# Hatch2021Trophy0805_2.net
KiCad netlist of a schematic drawn in EAGLE
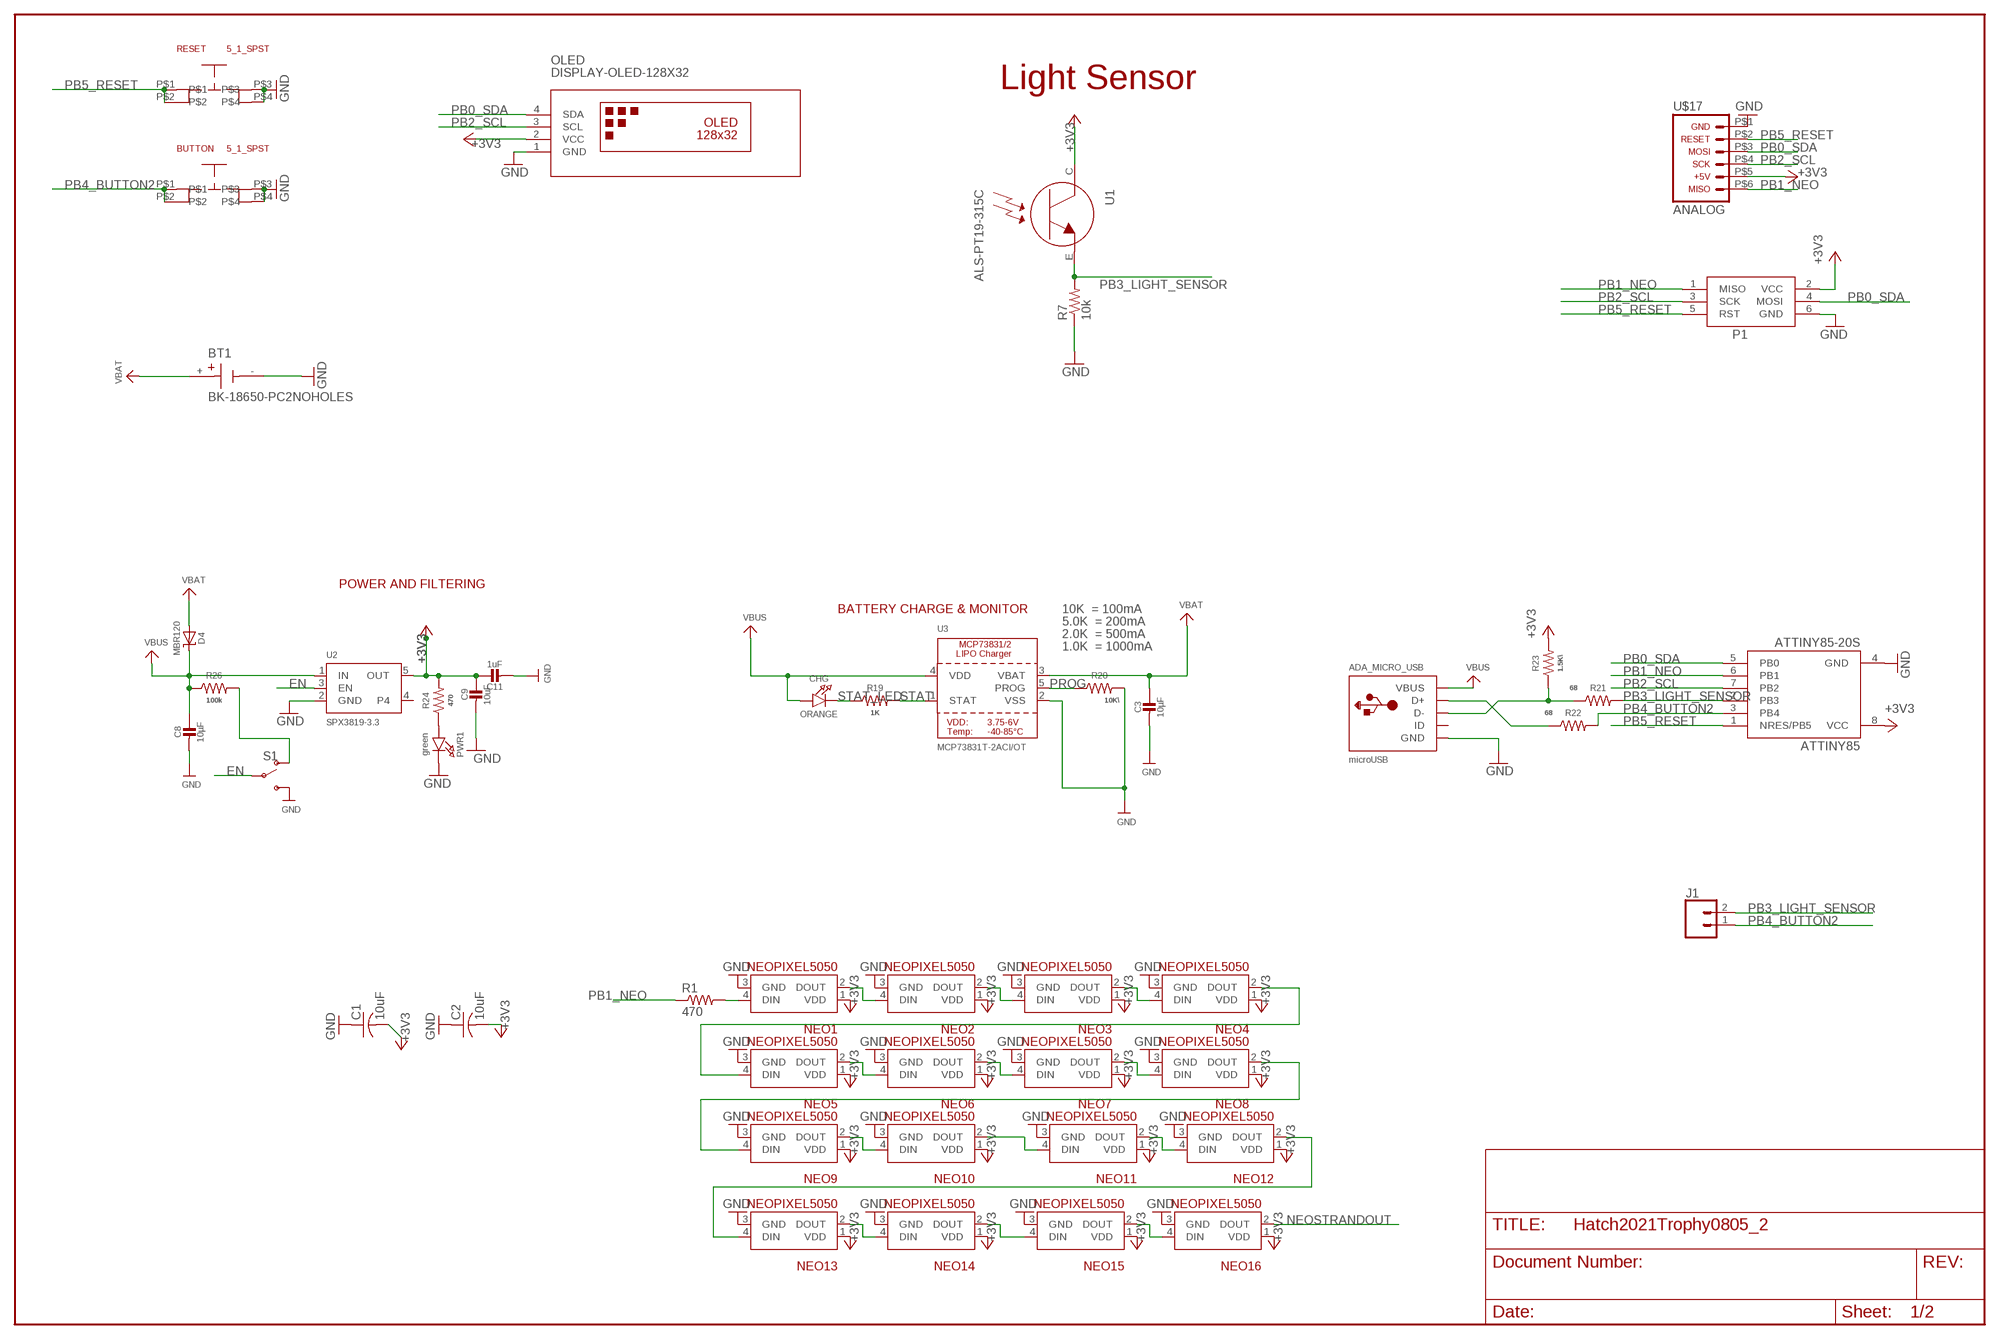
[diagram p0: schematic, sheet 1]

(export (version "E")
  (design (tool "Eeschema 10.0.6"))
  (components
    (comp (ref "ADA_MICRO_USB")
      (value "microUSB")
      (footprint "eagle-import:4UCONN_20329_V2")
      (libsource (lib "eagle-import") (part "USB_MICRO_20329_V2"))
    )
    (comp (ref "ATTINY85")
      (value "ATTINY85-20S")
      (footprint "eagle-import:SOIC8_EIAJ_208MIL")
      (libsource (lib "eagle-import") (part "ATTINY85S-20"))
    )
    (comp (ref "BT1")
      (value "BK-18650-PC2NOHOLES")
      (footprint "eagle-import:BAT_BK-18650-PC2_NOHOLES")
      (libsource (lib "eagle-import") (part "BK-18650-PC2NOHOLES"))
    )
    (comp (ref "BUTTON")
      (value "5_1_SPST")
      (footprint "eagle-import:5_1_SPST")
      (libsource (lib "eagle-import") (part "5_1_SPST"))
    )
    (comp (ref "C1")
      (value "10uF")
      (footprint "eagle-import:C0805")
      (libsource (lib "eagle-import") (part "C-USC0805"))
    )
    (comp (ref "C2")
      (value "10uF")
      (footprint "eagle-import:C0805")
      (libsource (lib "eagle-import") (part "C-USC0805"))
    )
    (comp (ref "C3")
      (value "10µF")
      (footprint "eagle-import:0805-NO@1")
      (libsource (lib "eagle-import") (part "CAP_CERAMIC0805-NOOUTLINE"))
    )
    (comp (ref "C8")
      (value "10µF")
      (footprint "eagle-import:0805-NO@1")
      (libsource (lib "eagle-import") (part "CAP_CERAMIC0805-NOOUTLINE"))
    )
    (comp (ref "C9")
      (value "10uF")
      (footprint "eagle-import:0805-NO@1")
      (libsource (lib "eagle-import") (part "CAP_CERAMIC0805-NOOUTLINE"))
    )
    (comp (ref "C11")
      (value "1uF")
      (footprint "eagle-import:0805-NO@1")
      (libsource (lib "eagle-import") (part "CAP_CERAMIC0805-NOOUTLINE"))
    )
    (comp (ref "CHG")
      (value "ORANGE")
      (footprint "eagle-import:CHIPLED_0805_NOOUTLINE")
      (libsource (lib "eagle-import") (part "LED0805_NOOUTLINE"))
    )
    (comp (ref "D4")
      (value "MBR120")
      (footprint "eagle-import:SOD-123")
      (libsource (lib "eagle-import") (part "DIODE-SCHOTTKYSOD-123"))
    )
    (comp (ref "J1")
      (value "CONN_02")
      (footprint "eagle-import:1X02")
      (libsource (lib "eagle-import") (part "CONN_02"))
    )
    (comp (ref "NEO1")
      (value "NEOPIXEL5050")
      (footprint "eagle-import:NEOPIXEL5050")
      (libsource (lib "eagle-import") (part "NEOPIXEL5050"))
    )
    (comp (ref "NEO2")
      (value "NEOPIXEL5050")
      (footprint "eagle-import:NEOPIXEL5050")
      (libsource (lib "eagle-import") (part "NEOPIXEL5050"))
    )
    (comp (ref "NEO3")
      (value "NEOPIXEL5050")
      (footprint "eagle-import:NEOPIXEL5050")
      (libsource (lib "eagle-import") (part "NEOPIXEL5050"))
    )
    (comp (ref "NEO4")
      (value "NEOPIXEL5050")
      (footprint "eagle-import:NEOPIXEL5050")
      (libsource (lib "eagle-import") (part "NEOPIXEL5050"))
    )
    (comp (ref "NEO5")
      (value "NEOPIXEL5050")
      (footprint "eagle-import:NEOPIXEL5050")
      (libsource (lib "eagle-import") (part "NEOPIXEL5050"))
    )
    (comp (ref "NEO6")
      (value "NEOPIXEL5050")
      (footprint "eagle-import:NEOPIXEL5050")
      (libsource (lib "eagle-import") (part "NEOPIXEL5050"))
    )
    (comp (ref "NEO7")
      (value "NEOPIXEL5050")
      (footprint "eagle-import:NEOPIXEL5050")
      (libsource (lib "eagle-import") (part "NEOPIXEL5050"))
    )
    (comp (ref "NEO8")
      (value "NEOPIXEL5050")
      (footprint "eagle-import:NEOPIXEL5050")
      (libsource (lib "eagle-import") (part "NEOPIXEL5050"))
    )
    (comp (ref "NEO9")
      (value "NEOPIXEL5050")
      (footprint "eagle-import:NEOPIXEL5050")
      (libsource (lib "eagle-import") (part "NEOPIXEL5050"))
    )
    (comp (ref "NEO10")
      (value "NEOPIXEL5050")
      (footprint "eagle-import:NEOPIXEL5050")
      (libsource (lib "eagle-import") (part "NEOPIXEL5050"))
    )
    (comp (ref "NEO11")
      (value "NEOPIXEL5050")
      (footprint "eagle-import:NEOPIXEL5050")
      (libsource (lib "eagle-import") (part "NEOPIXEL5050"))
    )
    (comp (ref "NEO12")
      (value "NEOPIXEL5050")
      (footprint "eagle-import:NEOPIXEL5050")
      (libsource (lib "eagle-import") (part "NEOPIXEL5050"))
    )
    (comp (ref "NEO13")
      (value "NEOPIXEL5050")
      (footprint "eagle-import:NEOPIXEL5050")
      (libsource (lib "eagle-import") (part "NEOPIXEL5050"))
    )
    (comp (ref "NEO14")
      (value "NEOPIXEL5050")
      (footprint "eagle-import:NEOPIXEL5050")
      (libsource (lib "eagle-import") (part "NEOPIXEL5050"))
    )
    (comp (ref "NEO15")
      (value "NEOPIXEL5050")
      (footprint "eagle-import:NEOPIXEL5050")
      (libsource (lib "eagle-import") (part "NEOPIXEL5050"))
    )
    (comp (ref "NEO16")
      (value "NEOPIXEL5050")
      (footprint "eagle-import:NEOPIXEL5050")
      (libsource (lib "eagle-import") (part "NEOPIXEL5050"))
    )
    (comp (ref "OLED")
      (value "DISPLAY-OLED-128X32")
      (footprint "eagle-import:DISPLAY-OLED-128X32")
      (libsource (lib "eagle-import") (part "DISPLAY-OLED-128X32"))
    )
    (comp (ref "P1")
      (value "AVRISP-6")
      (footprint "eagle-import:AVRISP")
      (libsource (lib "eagle-import") (part "AVRISP-6"))
    )
    (comp (ref "PWR1")
      (value "green")
      (footprint "eagle-import:CHIPLED_0805_NOOUTLINE")
      (libsource (lib "eagle-import") (part "LED0805_NOOUTLINE"))
    )
    (comp (ref "R1")
      (value "470")
      (footprint "eagle-import:R0805")
      (libsource (lib "eagle-import") (part "R-US_R0805"))
    )
    (comp (ref "R7")
      (value "10k")
      (footprint "eagle-import:R0805")
      (libsource (lib "eagle-import") (part "R-US_R0805"))
    )
    (comp (ref "R19")
      (value "1K")
      (footprint "eagle-import:R0805")
      (libsource (lib "eagle-import") (part "R-US_R0805"))
    )
    (comp (ref "R20")
      (value "10K\\")
      (footprint "eagle-import:R0805")
      (libsource (lib "eagle-import") (part "R-US_R0805"))
    )
    (comp (ref "R21")
      (value "68")
      (footprint "eagle-import:R0805")
      (libsource (lib "eagle-import") (part "R-US_R0805"))
    )
    (comp (ref "R22")
      (value "68")
      (footprint "eagle-import:R0805")
      (libsource (lib "eagle-import") (part "R-US_R0805"))
    )
    (comp (ref "R23")
      (value "1.5K\\")
      (footprint "eagle-import:R0805")
      (libsource (lib "eagle-import") (part "R-US_R0805"))
    )
    (comp (ref "R24")
      (value "470")
      (footprint "eagle-import:R0805")
      (libsource (lib "eagle-import") (part "R-US_R0805"))
    )
    (comp (ref "R26")
      (value "100k")
      (footprint "eagle-import:R0805")
      (libsource (lib "eagle-import") (part "R-US_R0805"))
    )
    (comp (ref "RESET")
      (value "5_1_SPST")
      (footprint "eagle-import:5_1_SPST")
      (libsource (lib "eagle-import") (part "5_1_SPST"))
    )
    (comp (ref "S1")
      (value "SWITCH-SPDT-SMD-AYZ0202")
      (footprint "eagle-import:SWITCH_DPDT_SMD_AYZ0202")
      (libsource (lib "eagle-import") (part "SWITCH-SPDT-SMD-AYZ0202"))
    )
    (comp (ref "U$17")
      (value "ICSP_FLATSMD_2X3")
      (footprint "eagle-import:CONN-SMD-2X3")
      (libsource (lib "eagle-import") (part "ICSP_FLATSMD_2X3"))
    )
    (comp (ref "U1")
      (value "ALS-PT19-315C")
      (footprint "eagle-import:ALS-PT19-315C")
      (libsource (lib "eagle-import") (part "LIGHT_ALS-PT19-315C"))
    )
    (comp (ref "U2")
      (value "SPX3819-3.3")
      (footprint "eagle-import:SOT23-5")
      (libsource (lib "eagle-import") (part "VREG_SOT23-5"))
    )
    (comp (ref "U3")
      (value "MCP73831T-2ACI/OT")
      (footprint "eagle-import:SOT23-5")
      (libsource (lib "eagle-import") (part "MCP73831/2"))
    )
  )
  (nets
    (net (code "1") (name "+3V3") (class "Default")
      (node (ref "ATTINY85") (pin "8") (pinfunction "VCC_8") (pintype "power_in"))
      (node (ref "C1") (pin "2") (pinfunction "2_2") (pintype "passive"))
      (node (ref "C11") (pin "1") (pinfunction "1_1") (pintype "passive"))
      (node (ref "C2") (pin "2") (pinfunction "2_2") (pintype "passive"))
      (node (ref "C9") (pin "1") (pinfunction "1_1") (pintype "passive"))
      (node (ref "NEO1") (pin "1") (pinfunction "VDD_1") (pintype "bidirectional"))
      (node (ref "NEO10") (pin "1") (pinfunction "VDD_1") (pintype "bidirectional"))
      (node (ref "NEO11") (pin "1") (pinfunction "VDD_1") (pintype "bidirectional"))
      (node (ref "NEO12") (pin "1") (pinfunction "VDD_1") (pintype "bidirectional"))
      (node (ref "NEO13") (pin "1") (pinfunction "VDD_1") (pintype "bidirectional"))
      (node (ref "NEO14") (pin "1") (pinfunction "VDD_1") (pintype "bidirectional"))
      (node (ref "NEO15") (pin "1") (pinfunction "VDD_1") (pintype "bidirectional"))
      (node (ref "NEO16") (pin "1") (pinfunction "VDD_1") (pintype "bidirectional"))
      (node (ref "NEO2") (pin "1") (pinfunction "VDD_1") (pintype "bidirectional"))
      (node (ref "NEO3") (pin "1") (pinfunction "VDD_1") (pintype "bidirectional"))
      (node (ref "NEO4") (pin "1") (pinfunction "VDD_1") (pintype "bidirectional"))
      (node (ref "NEO5") (pin "1") (pinfunction "VDD_1") (pintype "bidirectional"))
      (node (ref "NEO6") (pin "1") (pinfunction "VDD_1") (pintype "bidirectional"))
      (node (ref "NEO7") (pin "1") (pinfunction "VDD_1") (pintype "bidirectional"))
      (node (ref "NEO8") (pin "1") (pinfunction "VDD_1") (pintype "bidirectional"))
      (node (ref "NEO9") (pin "1") (pinfunction "VDD_1") (pintype "bidirectional"))
      (node (ref "OLED") (pin "2") (pinfunction "VCC_2") (pintype "power_in"))
      (node (ref "P1") (pin "2") (pinfunction "VCC_2") (pintype "power_in"))
      (node (ref "R23") (pin "2") (pinfunction "2_2") (pintype "passive"))
      (node (ref "R24") (pin "2") (pinfunction "2_2") (pintype "passive"))
      (node (ref "U$17") (pin "P$5") (pinfunction "5_P$5") (pintype "passive"))
      (node (ref "U1") (pin "C") (pinfunction "C_C") (pintype "bidirectional"))
      (node (ref "U2") (pin "5") (pinfunction "OUT_5") (pintype "power_in"))
    )
    (net (code "2") (name "EN") (class "Default")
      (node (ref "S1") (pin "2") (pinfunction "P_2") (pintype "passive"))
      (node (ref "U2") (pin "3") (pinfunction "EN_3") (pintype "input"))
    )
    (net (code "3") (name "GND") (class "Default")
      (node (ref "ADA_MICRO_USB") (pin "BASE@1") (pinfunction "GND_BASE@1") (pintype "power_in"))
      (node (ref "ADA_MICRO_USB") (pin "BASE@2") (pinfunction "GND_BASE@2") (pintype "power_in"))
      (node (ref "ADA_MICRO_USB") (pin "GND") (pinfunction "GND_GND") (pintype "power_in"))
      (node (ref "ADA_MICRO_USB") (pin "SPRT@1") (pinfunction "GND_SPRT@1") (pintype "power_in"))
      (node (ref "ADA_MICRO_USB") (pin "SPRT@2") (pinfunction "GND_SPRT@2") (pintype "power_in"))
      (node (ref "ADA_MICRO_USB") (pin "SPRT@3") (pinfunction "GND_SPRT@3") (pintype "power_in"))
      (node (ref "ADA_MICRO_USB") (pin "SPRT@4") (pinfunction "GND_SPRT@4") (pintype "power_in"))
      (node (ref "ATTINY85") (pin "4") (pinfunction "GND_4") (pintype "power_in"))
      (node (ref "BT1") (pin "-") (pinfunction "-_-") (pintype "passive"))
      (node (ref "BUTTON") (pin "P$3") (pinfunction "P$3_P$3") (pintype "bidirectional"))
      (node (ref "BUTTON") (pin "P$4") (pinfunction "P$4_P$4") (pintype "bidirectional"))
      (node (ref "C1") (pin "1") (pinfunction "1_1") (pintype "passive"))
      (node (ref "C11") (pin "2") (pinfunction "2_2") (pintype "passive"))
      (node (ref "C2") (pin "1") (pinfunction "1_1") (pintype "passive"))
      (node (ref "C3") (pin "2") (pinfunction "2_2") (pintype "passive"))
      (node (ref "C8") (pin "2") (pinfunction "2_2") (pintype "passive"))
      (node (ref "C9") (pin "2") (pinfunction "2_2") (pintype "passive"))
      (node (ref "NEO1") (pin "3") (pinfunction "GND_3") (pintype "bidirectional"))
      (node (ref "NEO10") (pin "3") (pinfunction "GND_3") (pintype "bidirectional"))
      (node (ref "NEO11") (pin "3") (pinfunction "GND_3") (pintype "bidirectional"))
      (node (ref "NEO12") (pin "3") (pinfunction "GND_3") (pintype "bidirectional"))
      (node (ref "NEO13") (pin "3") (pinfunction "GND_3") (pintype "bidirectional"))
      (node (ref "NEO14") (pin "3") (pinfunction "GND_3") (pintype "bidirectional"))
      (node (ref "NEO15") (pin "3") (pinfunction "GND_3") (pintype "bidirectional"))
      (node (ref "NEO16") (pin "3") (pinfunction "GND_3") (pintype "bidirectional"))
      (node (ref "NEO2") (pin "3") (pinfunction "GND_3") (pintype "bidirectional"))
      (node (ref "NEO3") (pin "3") (pinfunction "GND_3") (pintype "bidirectional"))
      (node (ref "NEO4") (pin "3") (pinfunction "GND_3") (pintype "bidirectional"))
      (node (ref "NEO5") (pin "3") (pinfunction "GND_3") (pintype "bidirectional"))
      (node (ref "NEO6") (pin "3") (pinfunction "GND_3") (pintype "bidirectional"))
      (node (ref "NEO7") (pin "3") (pinfunction "GND_3") (pintype "bidirectional"))
      (node (ref "NEO8") (pin "3") (pinfunction "GND_3") (pintype "bidirectional"))
      (node (ref "NEO9") (pin "3") (pinfunction "GND_3") (pintype "bidirectional"))
      (node (ref "OLED") (pin "1") (pinfunction "GND_1") (pintype "power_in"))
      (node (ref "P1") (pin "6") (pinfunction "GND_6") (pintype "power_in"))
      (node (ref "PWR1") (pin "C") (pinfunction "C_C") (pintype "passive"))
      (node (ref "R20") (pin "2") (pinfunction "2_2") (pintype "passive"))
      (node (ref "R7") (pin "1") (pinfunction "1_1") (pintype "passive"))
      (node (ref "RESET") (pin "P$3") (pinfunction "P$3_P$3") (pintype "bidirectional"))
      (node (ref "RESET") (pin "P$4") (pinfunction "P$4_P$4") (pintype "bidirectional"))
      (node (ref "S1") (pin "3") (pinfunction "S_3") (pintype "passive"))
      (node (ref "U$17") (pin "P$1") (pinfunction "1_P$1") (pintype "passive"))
      (node (ref "U2") (pin "2") (pinfunction "GND_2") (pintype "power_in"))
      (node (ref "U3") (pin "2") (pinfunction "VSS_2") (pintype "power_in"))
    )
    (net (code "4") (name "NEOSTRANDOUT") (class "Default")
      (node (ref "NEO16") (pin "2") (pinfunction "DOUT_2") (pintype "bidirectional"))
    )
    (net (code "5") (name "Net-(ADA_MICRO_USB-PadD+)") (class "Default")
      (node (ref "ADA_MICRO_USB") (pin "D+") (pinfunction "D+_D+") (pintype "bidirectional"))
      (node (ref "R22") (pin "1") (pinfunction "1_1") (pintype "passive"))
    )
    (net (code "6") (name "Net-(ADA_MICRO_USB-PadD-)") (class "Default")
      (node (ref "ADA_MICRO_USB") (pin "D-") (pinfunction "D-_D-") (pintype "bidirectional"))
      (node (ref "R21") (pin "1") (pinfunction "1_1") (pintype "passive"))
      (node (ref "R23") (pin "1") (pinfunction "1_1") (pintype "passive"))
    )
    (net (code "7") (name "Net-(NEO1-DIN)") (class "Default")
      (node (ref "NEO1") (pin "4") (pinfunction "DIN_4") (pintype "bidirectional"))
      (node (ref "R1") (pin "2") (pinfunction "2_2") (pintype "passive"))
    )
    (net (code "8") (name "Net-(NEO1-DOUT)") (class "Default")
      (node (ref "NEO1") (pin "2") (pinfunction "DOUT_2") (pintype "bidirectional"))
      (node (ref "NEO2") (pin "4") (pinfunction "DIN_4") (pintype "bidirectional"))
    )
    (net (code "9") (name "Net-(NEO2-DOUT)") (class "Default")
      (node (ref "NEO2") (pin "2") (pinfunction "DOUT_2") (pintype "bidirectional"))
      (node (ref "NEO3") (pin "4") (pinfunction "DIN_4") (pintype "bidirectional"))
    )
    (net (code "10") (name "Net-(NEO3-DOUT)") (class "Default")
      (node (ref "NEO3") (pin "2") (pinfunction "DOUT_2") (pintype "bidirectional"))
      (node (ref "NEO4") (pin "4") (pinfunction "DIN_4") (pintype "bidirectional"))
    )
    (net (code "11") (name "Net-(NEO4-DOUT)") (class "Default")
      (node (ref "NEO4") (pin "2") (pinfunction "DOUT_2") (pintype "bidirectional"))
      (node (ref "NEO5") (pin "4") (pinfunction "DIN_4") (pintype "bidirectional"))
    )
    (net (code "12") (name "Net-(NEO5-DOUT)") (class "Default")
      (node (ref "NEO5") (pin "2") (pinfunction "DOUT_2") (pintype "bidirectional"))
      (node (ref "NEO6") (pin "4") (pinfunction "DIN_4") (pintype "bidirectional"))
    )
    (net (code "13") (name "Net-(NEO6-DOUT)") (class "Default")
      (node (ref "NEO6") (pin "2") (pinfunction "DOUT_2") (pintype "bidirectional"))
      (node (ref "NEO7") (pin "4") (pinfunction "DIN_4") (pintype "bidirectional"))
    )
    (net (code "14") (name "Net-(NEO7-DOUT)") (class "Default")
      (node (ref "NEO7") (pin "2") (pinfunction "DOUT_2") (pintype "bidirectional"))
      (node (ref "NEO8") (pin "4") (pinfunction "DIN_4") (pintype "bidirectional"))
    )
    (net (code "15") (name "Net-(NEO8-DOUT)") (class "Default")
      (node (ref "NEO8") (pin "2") (pinfunction "DOUT_2") (pintype "bidirectional"))
      (node (ref "NEO9") (pin "4") (pinfunction "DIN_4") (pintype "bidirectional"))
    )
    (net (code "16") (name "Net-(NEO10-DIN)") (class "Default")
      (node (ref "NEO10") (pin "4") (pinfunction "DIN_4") (pintype "bidirectional"))
      (node (ref "NEO9") (pin "2") (pinfunction "DOUT_2") (pintype "bidirectional"))
    )
    (net (code "17") (name "Net-(NEO10-DOUT)") (class "Default")
      (node (ref "NEO10") (pin "2") (pinfunction "DOUT_2") (pintype "bidirectional"))
      (node (ref "NEO11") (pin "4") (pinfunction "DIN_4") (pintype "bidirectional"))
    )
    (net (code "18") (name "Net-(NEO11-DOUT)") (class "Default")
      (node (ref "NEO11") (pin "2") (pinfunction "DOUT_2") (pintype "bidirectional"))
      (node (ref "NEO12") (pin "4") (pinfunction "DIN_4") (pintype "bidirectional"))
    )
    (net (code "19") (name "Net-(NEO12-DOUT)") (class "Default")
      (node (ref "NEO12") (pin "2") (pinfunction "DOUT_2") (pintype "bidirectional"))
      (node (ref "NEO13") (pin "4") (pinfunction "DIN_4") (pintype "bidirectional"))
    )
    (net (code "20") (name "Net-(NEO13-DOUT)") (class "Default")
      (node (ref "NEO13") (pin "2") (pinfunction "DOUT_2") (pintype "bidirectional"))
      (node (ref "NEO14") (pin "4") (pinfunction "DIN_4") (pintype "bidirectional"))
    )
    (net (code "21") (name "Net-(NEO14-DOUT)") (class "Default")
      (node (ref "NEO14") (pin "2") (pinfunction "DOUT_2") (pintype "bidirectional"))
      (node (ref "NEO15") (pin "4") (pinfunction "DIN_4") (pintype "bidirectional"))
    )
    (net (code "22") (name "Net-(NEO15-DOUT)") (class "Default")
      (node (ref "NEO15") (pin "2") (pinfunction "DOUT_2") (pintype "bidirectional"))
      (node (ref "NEO16") (pin "4") (pinfunction "DIN_4") (pintype "bidirectional"))
    )
    (net (code "23") (name "Net-(PWR1-PadA)") (class "Default")
      (node (ref "PWR1") (pin "A") (pinfunction "A_A") (pintype "passive"))
      (node (ref "R24") (pin "1") (pinfunction "1_1") (pintype "passive"))
    )
    (net (code "24") (name "Net-(S1-O)") (class "Default")
      (node (ref "R26") (pin "2") (pinfunction "2_2") (pintype "passive"))
      (node (ref "S1") (pin "1") (pinfunction "O_1") (pintype "passive"))
    )
    (net (code "25") (name "PB0_SDA") (class "Default")
      (node (ref "ATTINY85") (pin "5") (pinfunction "PB0_5") (pintype "bidirectional"))
      (node (ref "OLED") (pin "4") (pinfunction "SDA_4") (pintype "bidirectional"))
      (node (ref "P1") (pin "4") (pinfunction "MOSI_4") (pintype "output"))
      (node (ref "U$17") (pin "P$3") (pinfunction "3_P$3") (pintype "passive"))
    )
    (net (code "26") (name "PB1_NEO") (class "Default")
      (node (ref "ATTINY85") (pin "6") (pinfunction "PB1_6") (pintype "bidirectional"))
      (node (ref "P1") (pin "1") (pinfunction "MISO_1") (pintype "input"))
      (node (ref "R1") (pin "1") (pinfunction "1_1") (pintype "passive"))
      (node (ref "U$17") (pin "P$6") (pinfunction "6_P$6") (pintype "passive"))
    )
    (net (code "27") (name "PB2_SCL") (class "Default")
      (node (ref "ATTINY85") (pin "7") (pinfunction "PB2_7") (pintype "bidirectional"))
      (node (ref "OLED") (pin "3") (pinfunction "SCL_3") (pintype "bidirectional"))
      (node (ref "P1") (pin "3") (pinfunction "SCK_3") (pintype "output"))
      (node (ref "U$17") (pin "P$4") (pinfunction "4_P$4") (pintype "passive"))
    )
    (net (code "28") (name "PB3_LIGHT_SENSOR") (class "Default")
      (node (ref "ATTINY85") (pin "2") (pinfunction "PB3_2") (pintype "bidirectional"))
      (node (ref "J1") (pin "2") (pinfunction "2_2") (pintype "passive"))
      (node (ref "R21") (pin "2") (pinfunction "2_2") (pintype "passive"))
      (node (ref "R7") (pin "2") (pinfunction "2_2") (pintype "passive"))
      (node (ref "U1") (pin "E") (pinfunction "E_E") (pintype "bidirectional"))
    )
    (net (code "29") (name "PB4_BUTTON2") (class "Default")
      (node (ref "ATTINY85") (pin "3") (pinfunction "PB4_3") (pintype "bidirectional"))
      (node (ref "BUTTON") (pin "P$1") (pinfunction "P$1_P$1") (pintype "bidirectional"))
      (node (ref "BUTTON") (pin "P$2") (pinfunction "P$2_P$2") (pintype "bidirectional"))
      (node (ref "J1") (pin "1") (pinfunction "1_1") (pintype "passive"))
      (node (ref "R22") (pin "2") (pinfunction "2_2") (pintype "passive"))
    )
    (net (code "30") (name "PB5_RESET") (class "Default")
      (node (ref "ATTINY85") (pin "1") (pinfunction "NRES/PB5_1") (pintype "bidirectional"))
      (node (ref "P1") (pin "5") (pinfunction "RST_5") (pintype "output"))
      (node (ref "RESET") (pin "P$1") (pinfunction "P$1_P$1") (pintype "bidirectional"))
      (node (ref "RESET") (pin "P$2") (pinfunction "P$2_P$2") (pintype "bidirectional"))
      (node (ref "U$17") (pin "P$2") (pinfunction "2_P$2") (pintype "passive"))
    )
    (net (code "31") (name "PROG") (class "Default")
      (node (ref "R20") (pin "1") (pinfunction "1_1") (pintype "passive"))
      (node (ref "U3") (pin "5") (pinfunction "PROG_5") (pintype "input"))
    )
    (net (code "32") (name "STAT") (class "Default")
      (node (ref "R19") (pin "2") (pinfunction "2_2") (pintype "passive"))
      (node (ref "U3") (pin "1") (pinfunction "STAT_1") (pintype "output"))
    )
    (net (code "33") (name "STAT_LED") (class "Default")
      (node (ref "CHG") (pin "C") (pinfunction "C_C") (pintype "passive"))
      (node (ref "R19") (pin "1") (pinfunction "1_1") (pintype "passive"))
    )
    (net (code "34") (name "VBAT") (class "Default")
      (node (ref "BT1") (pin "+") (pinfunction "+_+") (pintype "passive"))
      (node (ref "C3") (pin "1") (pinfunction "1_1") (pintype "passive"))
      (node (ref "D4") (pin "A") (pinfunction "A_A") (pintype "passive"))
      (node (ref "U3") (pin "3") (pinfunction "VBAT_3") (pintype "power_in"))
    )
    (net (code "35") (name "VBUS") (class "Default")
      (node (ref "ADA_MICRO_USB") (pin "VBUS") (pinfunction "VBUS_VBUS") (pintype "power_in"))
      (node (ref "C8") (pin "1") (pinfunction "1_1") (pintype "passive"))
      (node (ref "CHG") (pin "A") (pinfunction "A_A") (pintype "passive"))
      (node (ref "D4") (pin "C") (pinfunction "C_C") (pintype "passive"))
      (node (ref "R26") (pin "1") (pinfunction "1_1") (pintype "passive"))
      (node (ref "U2") (pin "1") (pinfunction "IN_1") (pintype "power_in"))
      (node (ref "U3") (pin "4") (pinfunction "VDD_4") (pintype "power_in"))
    )
    (net (code "36") (name "unconnected-(ADA_MICRO_USB-PadID)") (class "Default")
      (node (ref "ADA_MICRO_USB") (pin "ID") (pinfunction "ID_ID") (pintype "bidirectional"))
    )
    (net (code "37") (name "unconnected-(U2-P4-Pad4)") (class "Default")
      (node (ref "U2") (pin "4") (pinfunction "P4_4") (pintype "bidirectional"))
    )
  )
)
